# top_board.net
KiCad netlist of a schematic drawn in EAGLE
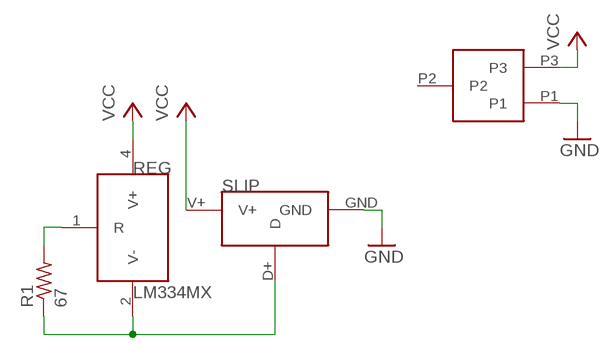
[diagram p0: schematic, sheet 1]

(export (version "E")
  (design (tool "Eeschema 10.0.6"))
  (components
    (comp (ref "R1")
      (value "67")
      (footprint "eagle-import:R0603")
      (libsource (lib "eagle-import") (part "R-US_R0603"))
    )
    (comp (ref "REG")
      (value "LM334MX")
      (footprint "eagle-import:8-SOIC")
      (libsource (lib "eagle-import") (part "LM334MX"))
    )
    (comp (ref "SLIP")
      (value "RING")
      (footprint "eagle-import:RING")
      (libsource (lib "eagle-import") (part "RING"))
    )
    (comp (ref "U$2")
      (value "AVX_CONN")
      (footprint "eagle-import:AVX_CONN")
      (libsource (lib "eagle-import") (part "AVX_CONN"))
    )
  )
  (nets
    (net (code "1") (name "GND") (class "Default")
      (node (ref "SLIP") (pin "GND") (pinfunction "GND_GND") (pintype "bidirectional"))
      (node (ref "U$2") (pin "P1") (pinfunction "P1_P1") (pintype "bidirectional"))
    )
    (net (code "2") (name "Net-(REG-R)") (class "Default")
      (node (ref "R1") (pin "2") (pinfunction "2_2") (pintype "passive"))
      (node (ref "REG") (pin "1") (pinfunction "R_1") (pintype "bidirectional"))
    )
    (net (code "3") (name "Net-(REG-V-)") (class "Default")
      (node (ref "R1") (pin "1") (pinfunction "1_1") (pintype "passive"))
      (node (ref "REG") (pin "2") (pinfunction "V-_2") (pintype "bidirectional"))
      (node (ref "SLIP") (pin "D+") (pinfunction "D_D+") (pintype "bidirectional"))
    )
    (net (code "4") (name "VCC") (class "Default")
      (node (ref "REG") (pin "4") (pinfunction "V+_4") (pintype "bidirectional"))
      (node (ref "SLIP") (pin "V+") (pinfunction "V+_V+") (pintype "bidirectional"))
      (node (ref "U$2") (pin "P3") (pinfunction "P3_P3") (pintype "bidirectional"))
    )
    (net (code "5") (name "unconnected-(U$2-PadP2)") (class "Default")
      (node (ref "U$2") (pin "P2") (pinfunction "P2_P2") (pintype "bidirectional"))
    )
  )
)
